# Power_Circuit.net
KiCad netlist of a schematic drawn in Altium Designer
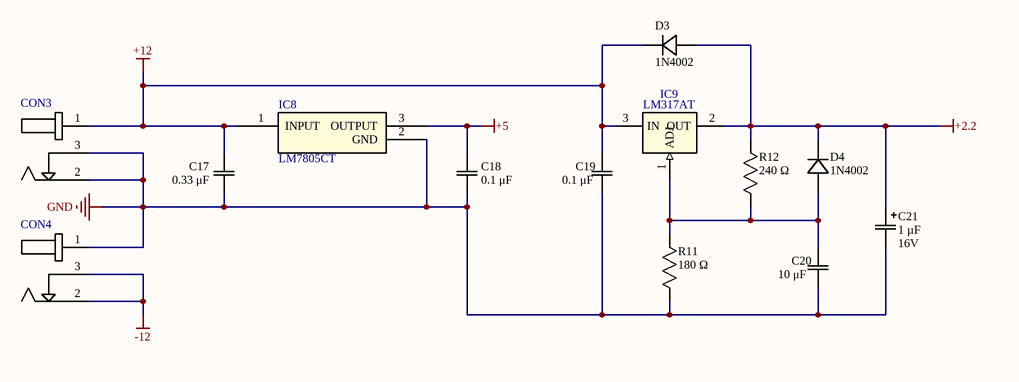
[diagram p0: Power Circuit.SchDoc]

(export (version "E")
  (design (tool "Eeschema 10.0.6"))
  (components
    (comp (ref "C17")
      (value "0.33 μF")
      (footprint "12062A270JAT2A:CAP_1206J")
      (description "Imported")
      (fields (field (name "MANUFACTURER_PART_NUMBER") "12062A270JAT2A"))
      (libsource (lib "12062A270JAT2A") (part "12062A270JAT2A"))
    )
    (comp (ref "C18")
      (value "0.1 μF")
      (footprint "12062A270JAT2A:CAP_1206J")
      (description "Imported")
      (fields (field (name "MANUFACTURER_PART_NUMBER") "12062A270JAT2A"))
      (libsource (lib "12062A270JAT2A") (part "12062A270JAT2A"))
    )
    (comp (ref "C19")
      (value "0.1 μF")
      (footprint "12062A270JAT2A:CAP_1206J")
      (description "Imported")
      (fields (field (name "MANUFACTURER_PART_NUMBER") "12062A270JAT2A"))
      (libsource (lib "12062A270JAT2A") (part "12062A270JAT2A"))
    )
    (comp (ref "C20")
      (value "10 μF")
      (footprint "12062A270JAT2A:CAP_1206J")
      (description "Imported")
      (fields (field (name "MANUFACTURER_PART_NUMBER") "12062A270JAT2A"))
      (libsource (lib "12062A270JAT2A") (part "12062A270JAT2A"))
    )
    (comp (ref "C21")
      (value "1 µF")
      (footprint "EEE-1CA221UP:EEE-1C")
      (description "Imported")
      (fields
        (field (name "MANUFACTURER_PART_NUMBER") "EEE-1CA221UP")
        (field (name "VOLTAGE") "16V")
        (field (name "COPYRIGHT") "Copyright (C) 2015 Accelerated Designs. All rights reserved")
      )
      (libsource (lib "EEE-1CA221UP") (part "EEE-1CA221UP"))
    )
    (comp (ref "CON3")
      (value "DCJ250-10-A_XX-X_revA")
      (footprint "DCJ250-10-A-XX-X_revA:DCJ250-10-A_XX-X_revA")
      (description "DC Power Jack, Thru-Hole, Horizontal, with Locating Pegs, D2.5mm")
      (libsource (lib "DCJ250-10-A_XX-X_revA") (part "DCJ250-10-A_XX-X_revA"))
    )
    (comp (ref "CON4")
      (value "DCJ250-10-A_XX-X_revA")
      (footprint "DCJ250-10-A-XX-X_revA:DCJ250-10-A_XX-X_revA")
      (description "DC Power Jack, Thru-Hole, Horizontal, with Locating Pegs, D2.5mm")
      (libsource (lib "DCJ250-10-A_XX-X_revA") (part "DCJ250-10-A_XX-X_revA"))
    )
    (comp (ref "D3")
      (value "1N4002")
      (footprint "1N4002:DO-204AL")
      (description "Imported")
      (fields (field (name "MANUFACTURER_PART_NUMBER") "1N4002-E3/73"))
      (libsource (lib "1N4002") (part "1N4002-E3/73"))
    )
    (comp (ref "D4")
      (value "1N4002")
      (footprint "1N4002:DO-204AL")
      (description "Imported")
      (fields (field (name "MANUFACTURER_PART_NUMBER") "1N4002-E3/73"))
      (libsource (lib "1N4002") (part "1N4002-E3/73"))
    )
    (comp (ref "IC8")
      (value "LM7805CT")
      (footprint "LM7805CT:TO-220")
      (description "Imported")
      (libsource (lib "LM7805CT") (part "LM7805CT"))
    )
    (comp (ref "IC9")
      (value "LM317AT")
      (footprint "LM317AT:T03B")
      (description "Imported")
      (libsource (lib "LM317AT") (part "LM317AT"))
    )
    (comp (ref "R11")
      (value "180 Ω")
      (footprint "RC1206JR-071M1L:RC1206N")
      (description "Imported")
      (fields (field (name "MANUFACTURER_PART_NUMBER") "RC1206JR-071M1L"))
      (libsource (lib "RC1206JR-071M1L") (part "RC1206JR-071M1L"))
    )
    (comp (ref "R12")
      (value "240 Ω")
      (footprint "RC1206JR-071M1L:RC1206N")
      (description "Imported")
      (fields (field (name "MANUFACTURER_PART_NUMBER") "RC1206JR-071M1L"))
      (libsource (lib "RC1206JR-071M1L") (part "RC1206JR-071M1L"))
    )
  )
  (nets
    (net (code "1") (name "+2.2") (class "Default")
      (node (ref "C21") (pin "1") (pinfunction "1_1") (pintype "passive"))
      (node (ref "D3") (pin "2") (pinfunction "2_2") (pintype "passive"))
      (node (ref "D4") (pin "1") (pinfunction "1_1") (pintype "passive"))
      (node (ref "IC9") (pin "2") (pinfunction "OUT_2") (pintype "power_in"))
      (node (ref "R12") (pin "1") (pinfunction "1_1") (pintype "passive"))
    )
    (net (code "2") (name "+5") (class "Default")
      (node (ref "C18") (pin "2") (pinfunction "2_2") (pintype "passive"))
      (node (ref "IC8") (pin "3") (pinfunction "OUTPUT_3") (pintype "power_in"))
    )
    (net (code "3") (name "+12") (class "Default")
      (node (ref "C17") (pin "2") (pinfunction "2_2") (pintype "passive"))
      (node (ref "C19") (pin "2") (pinfunction "2_2") (pintype "passive"))
      (node (ref "CON3") (pin "1") (pintype "power_in"))
      (node (ref "D3") (pin "1") (pinfunction "1_1") (pintype "passive"))
      (node (ref "IC8") (pin "1") (pinfunction "INPUT_1") (pintype "power_in"))
      (node (ref "IC9") (pin "3") (pinfunction "IN_3") (pintype "power_in"))
    )
    (net (code "4") (name "-12") (class "Default")
      (node (ref "CON4") (pin "2") (pintype "power_in"))
      (node (ref "CON4") (pin "3") (pintype "power_in"))
    )
    (net (code "5") (name "GND") (class "Default")
      (node (ref "C17") (pin "1") (pinfunction "1_1") (pintype "passive"))
      (node (ref "C18") (pin "1") (pinfunction "1_1") (pintype "passive"))
      (node (ref "C19") (pin "1") (pinfunction "1_1") (pintype "passive"))
      (node (ref "C20") (pin "1") (pinfunction "1_1") (pintype "passive"))
      (node (ref "C21") (pin "2") (pinfunction "2_2") (pintype "passive"))
      (node (ref "CON3") (pin "2") (pintype "power_in"))
      (node (ref "CON3") (pin "3") (pintype "power_in"))
      (node (ref "CON4") (pin "1") (pintype "power_in"))
      (node (ref "IC8") (pin "2") (pinfunction "GND_2") (pintype "power_in"))
      (node (ref "R11") (pin "2") (pinfunction "2_2") (pintype "passive"))
    )
    (net (code "6") (name "Net-(IC9-ADJ)") (class "Default")
      (node (ref "C20") (pin "2") (pinfunction "2_2") (pintype "passive"))
      (node (ref "D4") (pin "2") (pinfunction "2_2") (pintype "passive"))
      (node (ref "IC9") (pin "1") (pinfunction "ADJ_1") (pintype "input"))
      (node (ref "R11") (pin "1") (pinfunction "1_1") (pintype "passive"))
      (node (ref "R12") (pin "2") (pinfunction "2_2") (pintype "passive"))
    )
  )
)
